# tappytap_v6_AoA_6x6.net
KiCad netlist of a schematic drawn in EAGLE
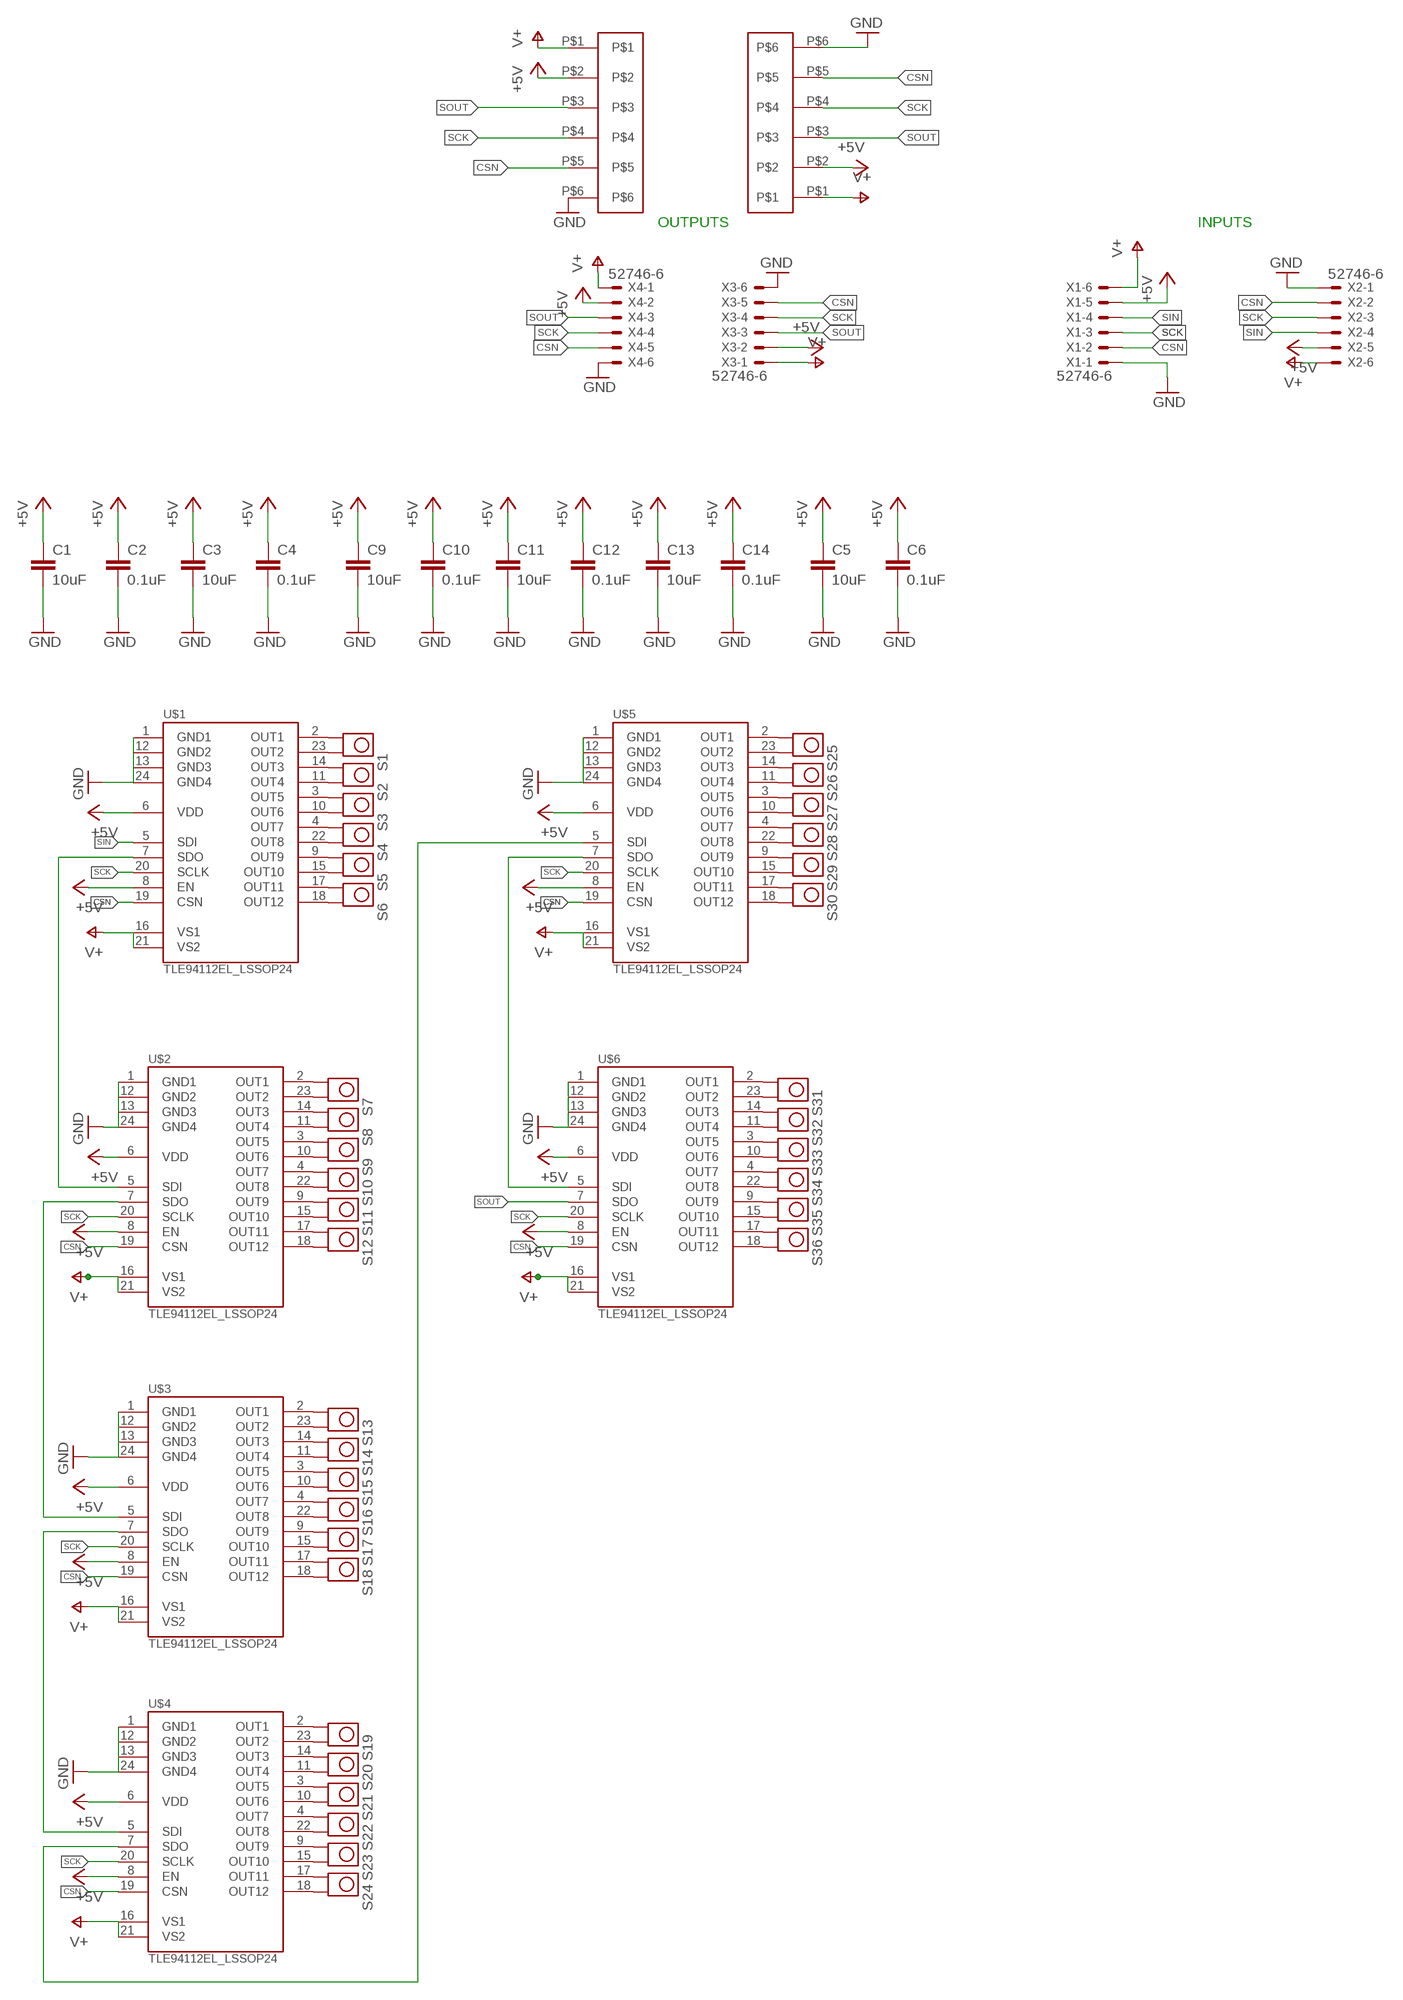
[diagram p0: schematic, sheet 1]

(export (version "E")
  (design (tool "Eeschema 10.0.6"))
  (components
    (comp (ref "C1")
      (value "10uF")
      (footprint "eagle-import:C0603")
      (libsource (lib "eagle-import") (part "C-EUC0603"))
    )
    (comp (ref "C2")
      (value "0.1uF")
      (footprint "eagle-import:C0603")
      (libsource (lib "eagle-import") (part "C-EUC0603"))
    )
    (comp (ref "C3")
      (value "10uF")
      (footprint "eagle-import:C0603")
      (libsource (lib "eagle-import") (part "C-EUC0603"))
    )
    (comp (ref "C4")
      (value "0.1uF")
      (footprint "eagle-import:C0603")
      (libsource (lib "eagle-import") (part "C-EUC0603"))
    )
    (comp (ref "C5")
      (value "10uF")
      (footprint "eagle-import:C0603")
      (libsource (lib "eagle-import") (part "C-EUC0603"))
    )
    (comp (ref "C6")
      (value "0.1uF")
      (footprint "eagle-import:C0603")
      (libsource (lib "eagle-import") (part "C-EUC0603"))
    )
    (comp (ref "C9")
      (value "10uF")
      (footprint "eagle-import:C0603")
      (libsource (lib "eagle-import") (part "C-EUC0603"))
    )
    (comp (ref "C10")
      (value "0.1uF")
      (footprint "eagle-import:C0603")
      (libsource (lib "eagle-import") (part "C-EUC0603"))
    )
    (comp (ref "C11")
      (value "10uF")
      (footprint "eagle-import:C0603")
      (libsource (lib "eagle-import") (part "C-EUC0603"))
    )
    (comp (ref "C12")
      (value "0.1uF")
      (footprint "eagle-import:C0603")
      (libsource (lib "eagle-import") (part "C-EUC0603"))
    )
    (comp (ref "C13")
      (value "10uF")
      (footprint "eagle-import:C0603")
      (libsource (lib "eagle-import") (part "C-EUC0603"))
    )
    (comp (ref "C14")
      (value "0.1uF")
      (footprint "eagle-import:C0603")
      (libsource (lib "eagle-import") (part "C-EUC0603"))
    )
    (comp (ref "S1")
      (value "TP_4MM_MED_PAD")
      (footprint "eagle-import:TP_4MM_MED_PAD")
      (libsource (lib "eagle-import") (part "TP_4MM_MED_PAD"))
    )
    (comp (ref "S2")
      (value "TP_4MM_MED_PAD")
      (footprint "eagle-import:TP_4MM_MED_PAD")
      (libsource (lib "eagle-import") (part "TP_4MM_MED_PAD"))
    )
    (comp (ref "S3")
      (value "TP_4MM_MED_PAD")
      (footprint "eagle-import:TP_4MM_MED_PAD")
      (libsource (lib "eagle-import") (part "TP_4MM_MED_PAD"))
    )
    (comp (ref "S4")
      (value "TP_4MM_MED_PAD")
      (footprint "eagle-import:TP_4MM_MED_PAD")
      (libsource (lib "eagle-import") (part "TP_4MM_MED_PAD"))
    )
    (comp (ref "S5")
      (value "TP_4MM_MED_PAD")
      (footprint "eagle-import:TP_4MM_MED_PAD")
      (libsource (lib "eagle-import") (part "TP_4MM_MED_PAD"))
    )
    (comp (ref "S6")
      (value "TP_4MM_MED_PAD")
      (footprint "eagle-import:TP_4MM_MED_PAD")
      (libsource (lib "eagle-import") (part "TP_4MM_MED_PAD"))
    )
    (comp (ref "S7")
      (value "TP_4MM_MED_PAD")
      (footprint "eagle-import:TP_4MM_MED_PAD")
      (libsource (lib "eagle-import") (part "TP_4MM_MED_PAD"))
    )
    (comp (ref "S8")
      (value "TP_4MM_MED_PAD")
      (footprint "eagle-import:TP_4MM_MED_PAD")
      (libsource (lib "eagle-import") (part "TP_4MM_MED_PAD"))
    )
    (comp (ref "S9")
      (value "TP_4MM_MED_PAD")
      (footprint "eagle-import:TP_4MM_MED_PAD")
      (libsource (lib "eagle-import") (part "TP_4MM_MED_PAD"))
    )
    (comp (ref "S10")
      (value "TP_4MM_MED_PAD")
      (footprint "eagle-import:TP_4MM_MED_PAD")
      (libsource (lib "eagle-import") (part "TP_4MM_MED_PAD"))
    )
    (comp (ref "S11")
      (value "TP_4MM_MED_PAD")
      (footprint "eagle-import:TP_4MM_MED_PAD")
      (libsource (lib "eagle-import") (part "TP_4MM_MED_PAD"))
    )
    (comp (ref "S12")
      (value "TP_4MM_MED_PAD")
      (footprint "eagle-import:TP_4MM_MED_PAD")
      (libsource (lib "eagle-import") (part "TP_4MM_MED_PAD"))
    )
    (comp (ref "S13")
      (value "TP_4MM_MED_PAD")
      (footprint "eagle-import:TP_4MM_MED_PAD")
      (libsource (lib "eagle-import") (part "TP_4MM_MED_PAD"))
    )
    (comp (ref "S14")
      (value "TP_4MM_MED_PAD")
      (footprint "eagle-import:TP_4MM_MED_PAD")
      (libsource (lib "eagle-import") (part "TP_4MM_MED_PAD"))
    )
    (comp (ref "S15")
      (value "TP_4MM_MED_PAD")
      (footprint "eagle-import:TP_4MM_MED_PAD")
      (libsource (lib "eagle-import") (part "TP_4MM_MED_PAD"))
    )
    (comp (ref "S16")
      (value "TP_4MM_MED_PAD")
      (footprint "eagle-import:TP_4MM_MED_PAD")
      (libsource (lib "eagle-import") (part "TP_4MM_MED_PAD"))
    )
    (comp (ref "S17")
      (value "TP_4MM_MED_PAD")
      (footprint "eagle-import:TP_4MM_MED_PAD")
      (libsource (lib "eagle-import") (part "TP_4MM_MED_PAD"))
    )
    (comp (ref "S18")
      (value "TP_4MM_MED_PAD")
      (footprint "eagle-import:TP_4MM_MED_PAD")
      (libsource (lib "eagle-import") (part "TP_4MM_MED_PAD"))
    )
    (comp (ref "S19")
      (value "TP_4MM_MED_PAD")
      (footprint "eagle-import:TP_4MM_MED_PAD")
      (libsource (lib "eagle-import") (part "TP_4MM_MED_PAD"))
    )
    (comp (ref "S20")
      (value "TP_4MM_MED_PAD")
      (footprint "eagle-import:TP_4MM_MED_PAD")
      (libsource (lib "eagle-import") (part "TP_4MM_MED_PAD"))
    )
    (comp (ref "S21")
      (value "TP_4MM_MED_PAD")
      (footprint "eagle-import:TP_4MM_MED_PAD")
      (libsource (lib "eagle-import") (part "TP_4MM_MED_PAD"))
    )
    (comp (ref "S22")
      (value "TP_4MM_MED_PAD")
      (footprint "eagle-import:TP_4MM_MED_PAD")
      (libsource (lib "eagle-import") (part "TP_4MM_MED_PAD"))
    )
    (comp (ref "S23")
      (value "TP_4MM_MED_PAD")
      (footprint "eagle-import:TP_4MM_MED_PAD")
      (libsource (lib "eagle-import") (part "TP_4MM_MED_PAD"))
    )
    (comp (ref "S24")
      (value "TP_4MM_MED_PAD")
      (footprint "eagle-import:TP_4MM_MED_PAD")
      (libsource (lib "eagle-import") (part "TP_4MM_MED_PAD"))
    )
    (comp (ref "S25")
      (value "TP_4MM_MED_PAD")
      (footprint "eagle-import:TP_4MM_MED_PAD")
      (libsource (lib "eagle-import") (part "TP_4MM_MED_PAD"))
    )
    (comp (ref "S26")
      (value "TP_4MM_MED_PAD")
      (footprint "eagle-import:TP_4MM_MED_PAD")
      (libsource (lib "eagle-import") (part "TP_4MM_MED_PAD"))
    )
    (comp (ref "S27")
      (value "TP_4MM_MED_PAD")
      (footprint "eagle-import:TP_4MM_MED_PAD")
      (libsource (lib "eagle-import") (part "TP_4MM_MED_PAD"))
    )
    (comp (ref "S28")
      (value "TP_4MM_MED_PAD")
      (footprint "eagle-import:TP_4MM_MED_PAD")
      (libsource (lib "eagle-import") (part "TP_4MM_MED_PAD"))
    )
    (comp (ref "S29")
      (value "TP_4MM_MED_PAD")
      (footprint "eagle-import:TP_4MM_MED_PAD")
      (libsource (lib "eagle-import") (part "TP_4MM_MED_PAD"))
    )
    (comp (ref "S30")
      (value "TP_4MM_MED_PAD")
      (footprint "eagle-import:TP_4MM_MED_PAD")
      (libsource (lib "eagle-import") (part "TP_4MM_MED_PAD"))
    )
    (comp (ref "S31")
      (value "TP_4MM_MED_PAD")
      (footprint "eagle-import:TP_4MM_MED_PAD")
      (libsource (lib "eagle-import") (part "TP_4MM_MED_PAD"))
    )
    (comp (ref "S32")
      (value "TP_4MM_MED_PAD")
      (footprint "eagle-import:TP_4MM_MED_PAD")
      (libsource (lib "eagle-import") (part "TP_4MM_MED_PAD"))
    )
    (comp (ref "S33")
      (value "TP_4MM_MED_PAD")
      (footprint "eagle-import:TP_4MM_MED_PAD")
      (libsource (lib "eagle-import") (part "TP_4MM_MED_PAD"))
    )
    (comp (ref "S34")
      (value "TP_4MM_MED_PAD")
      (footprint "eagle-import:TP_4MM_MED_PAD")
      (libsource (lib "eagle-import") (part "TP_4MM_MED_PAD"))
    )
    (comp (ref "S35")
      (value "TP_4MM_MED_PAD")
      (footprint "eagle-import:TP_4MM_MED_PAD")
      (libsource (lib "eagle-import") (part "TP_4MM_MED_PAD"))
    )
    (comp (ref "S36")
      (value "TP_4MM_MED_PAD")
      (footprint "eagle-import:TP_4MM_MED_PAD")
      (libsource (lib "eagle-import") (part "TP_4MM_MED_PAD"))
    )
    (comp (ref "U$1")
      (value "TLE94112EL_LSSOP24")
      (footprint "eagle-import:SSOP-24")
      (libsource (lib "eagle-import") (part "TLE94112EL_LSSOP24"))
    )
    (comp (ref "U$2")
      (value "TLE94112EL_LSSOP24")
      (footprint "eagle-import:SSOP-24")
      (libsource (lib "eagle-import") (part "TLE94112EL_LSSOP24"))
    )
    (comp (ref "U$3")
      (value "TLE94112EL_LSSOP24")
      (footprint "eagle-import:SSOP-24")
      (libsource (lib "eagle-import") (part "TLE94112EL_LSSOP24"))
    )
    (comp (ref "U$4")
      (value "TLE94112EL_LSSOP24")
      (footprint "eagle-import:SSOP-24")
      (libsource (lib "eagle-import") (part "TLE94112EL_LSSOP24"))
    )
    (comp (ref "U$5")
      (value "TLE94112EL_LSSOP24")
      (footprint "eagle-import:SSOP-24")
      (libsource (lib "eagle-import") (part "TLE94112EL_LSSOP24"))
    )
    (comp (ref "U$6")
      (value "TLE94112EL_LSSOP24")
      (footprint "eagle-import:SSOP-24")
      (libsource (lib "eagle-import") (part "TLE94112EL_LSSOP24"))
    )
    (comp (ref "U$15")
      (value "FLEXTAB_6POS")
      (footprint "eagle-import:FLEXTAB_6POS")
      (libsource (lib "eagle-import") (part "FLEXTAB_6POS"))
    )
    (comp (ref "U$16")
      (value "FLEXTAB_6POS")
      (footprint "eagle-import:FLEXTAB_6POS")
      (libsource (lib "eagle-import") (part "FLEXTAB_6POS"))
    )
    (comp (ref "X1")
      (value "52746-6")
      (footprint "eagle-import:52746-6")
      (libsource (lib "eagle-import") (part "52746-6"))
    )
    (comp (ref "X2")
      (value "52746-6")
      (footprint "eagle-import:52746-6")
      (libsource (lib "eagle-import") (part "52746-6"))
    )
    (comp (ref "X3")
      (value "52746-6")
      (footprint "eagle-import:52746-6")
      (libsource (lib "eagle-import") (part "52746-6"))
    )
    (comp (ref "X4")
      (value "52746-6")
      (footprint "eagle-import:52746-6")
      (libsource (lib "eagle-import") (part "52746-6"))
    )
  )
  (nets
    (net (code "1") (name "+5V") (class "Default")
      (node (ref "C1") (pin "1") (pinfunction "1_1") (pintype "passive"))
      (node (ref "C10") (pin "1") (pinfunction "1_1") (pintype "passive"))
      (node (ref "C11") (pin "1") (pinfunction "1_1") (pintype "passive"))
      (node (ref "C12") (pin "1") (pinfunction "1_1") (pintype "passive"))
      (node (ref "C13") (pin "1") (pinfunction "1_1") (pintype "passive"))
      (node (ref "C14") (pin "1") (pinfunction "1_1") (pintype "passive"))
      (node (ref "C2") (pin "1") (pinfunction "1_1") (pintype "passive"))
      (node (ref "C3") (pin "1") (pinfunction "1_1") (pintype "passive"))
      (node (ref "C4") (pin "1") (pinfunction "1_1") (pintype "passive"))
      (node (ref "C5") (pin "1") (pinfunction "1_1") (pintype "passive"))
      (node (ref "C6") (pin "1") (pinfunction "1_1") (pintype "passive"))
      (node (ref "C9") (pin "1") (pinfunction "1_1") (pintype "passive"))
      (node (ref "U$1") (pin "6") (pinfunction "VDD_6") (pintype "bidirectional"))
      (node (ref "U$1") (pin "8") (pinfunction "EN_8") (pintype "bidirectional"))
      (node (ref "U$15") (pin "P$2") (pinfunction "P$2_P$2") (pintype "bidirectional"))
      (node (ref "U$16") (pin "P$2") (pinfunction "P$2_P$2") (pintype "bidirectional"))
      (node (ref "U$2") (pin "6") (pinfunction "VDD_6") (pintype "bidirectional"))
      (node (ref "U$2") (pin "8") (pinfunction "EN_8") (pintype "bidirectional"))
      (node (ref "U$3") (pin "6") (pinfunction "VDD_6") (pintype "bidirectional"))
      (node (ref "U$3") (pin "8") (pinfunction "EN_8") (pintype "bidirectional"))
      (node (ref "U$4") (pin "6") (pinfunction "VDD_6") (pintype "bidirectional"))
      (node (ref "U$4") (pin "8") (pinfunction "EN_8") (pintype "bidirectional"))
      (node (ref "U$5") (pin "6") (pinfunction "VDD_6") (pintype "bidirectional"))
      (node (ref "U$5") (pin "8") (pinfunction "EN_8") (pintype "bidirectional"))
      (node (ref "U$6") (pin "6") (pinfunction "VDD_6") (pintype "bidirectional"))
      (node (ref "U$6") (pin "8") (pinfunction "EN_8") (pintype "bidirectional"))
      (node (ref "X1") (pin "5") (pinfunction "S_5") (pintype "passive"))
      (node (ref "X2") (pin "5") (pinfunction "S_5") (pintype "passive"))
      (node (ref "X3") (pin "2") (pinfunction "S_2") (pintype "passive"))
      (node (ref "X4") (pin "2") (pinfunction "S_2") (pintype "passive"))
    )
    (net (code "2") (name "CSN") (class "Default")
      (node (ref "U$1") (pin "19") (pinfunction "CSN_19") (pintype "bidirectional"))
      (node (ref "U$15") (pin "P$5") (pinfunction "P$5_P$5") (pintype "bidirectional"))
      (node (ref "U$16") (pin "P$5") (pinfunction "P$5_P$5") (pintype "bidirectional"))
      (node (ref "U$2") (pin "19") (pinfunction "CSN_19") (pintype "bidirectional"))
      (node (ref "U$3") (pin "19") (pinfunction "CSN_19") (pintype "bidirectional"))
      (node (ref "U$4") (pin "19") (pinfunction "CSN_19") (pintype "bidirectional"))
      (node (ref "U$5") (pin "19") (pinfunction "CSN_19") (pintype "bidirectional"))
      (node (ref "U$6") (pin "19") (pinfunction "CSN_19") (pintype "bidirectional"))
      (node (ref "X1") (pin "2") (pinfunction "S_2") (pintype "passive"))
      (node (ref "X2") (pin "2") (pinfunction "S_2") (pintype "passive"))
      (node (ref "X3") (pin "5") (pinfunction "S_5") (pintype "passive"))
      (node (ref "X4") (pin "5") (pinfunction "S_5") (pintype "passive"))
    )
    (net (code "3") (name "GND") (class "Default")
      (node (ref "C1") (pin "2") (pinfunction "2_2") (pintype "passive"))
      (node (ref "C10") (pin "2") (pinfunction "2_2") (pintype "passive"))
      (node (ref "C11") (pin "2") (pinfunction "2_2") (pintype "passive"))
      (node (ref "C12") (pin "2") (pinfunction "2_2") (pintype "passive"))
      (node (ref "C13") (pin "2") (pinfunction "2_2") (pintype "passive"))
      (node (ref "C14") (pin "2") (pinfunction "2_2") (pintype "passive"))
      (node (ref "C2") (pin "2") (pinfunction "2_2") (pintype "passive"))
      (node (ref "C3") (pin "2") (pinfunction "2_2") (pintype "passive"))
      (node (ref "C4") (pin "2") (pinfunction "2_2") (pintype "passive"))
      (node (ref "C5") (pin "2") (pinfunction "2_2") (pintype "passive"))
      (node (ref "C6") (pin "2") (pinfunction "2_2") (pintype "passive"))
      (node (ref "C9") (pin "2") (pinfunction "2_2") (pintype "passive"))
      (node (ref "U$1") (pin "1") (pinfunction "GND1_1") (pintype "bidirectional"))
      (node (ref "U$1") (pin "12") (pinfunction "GND2_12") (pintype "bidirectional"))
      (node (ref "U$1") (pin "13") (pinfunction "GND3_13") (pintype "bidirectional"))
      (node (ref "U$1") (pin "24") (pinfunction "GND4_24") (pintype "bidirectional"))
      (node (ref "U$15") (pin "P$6") (pinfunction "P$6_P$6") (pintype "bidirectional"))
      (node (ref "U$16") (pin "P$6") (pinfunction "P$6_P$6") (pintype "bidirectional"))
      (node (ref "U$2") (pin "1") (pinfunction "GND1_1") (pintype "bidirectional"))
      (node (ref "U$2") (pin "12") (pinfunction "GND2_12") (pintype "bidirectional"))
      (node (ref "U$2") (pin "13") (pinfunction "GND3_13") (pintype "bidirectional"))
      (node (ref "U$2") (pin "24") (pinfunction "GND4_24") (pintype "bidirectional"))
      (node (ref "U$3") (pin "1") (pinfunction "GND1_1") (pintype "bidirectional"))
      (node (ref "U$3") (pin "12") (pinfunction "GND2_12") (pintype "bidirectional"))
      (node (ref "U$3") (pin "13") (pinfunction "GND3_13") (pintype "bidirectional"))
      (node (ref "U$3") (pin "24") (pinfunction "GND4_24") (pintype "bidirectional"))
      (node (ref "U$4") (pin "1") (pinfunction "GND1_1") (pintype "bidirectional"))
      (node (ref "U$4") (pin "12") (pinfunction "GND2_12") (pintype "bidirectional"))
      (node (ref "U$4") (pin "13") (pinfunction "GND3_13") (pintype "bidirectional"))
      (node (ref "U$4") (pin "24") (pinfunction "GND4_24") (pintype "bidirectional"))
      (node (ref "U$5") (pin "1") (pinfunction "GND1_1") (pintype "bidirectional"))
      (node (ref "U$5") (pin "12") (pinfunction "GND2_12") (pintype "bidirectional"))
      (node (ref "U$5") (pin "13") (pinfunction "GND3_13") (pintype "bidirectional"))
      (node (ref "U$5") (pin "24") (pinfunction "GND4_24") (pintype "bidirectional"))
      (node (ref "U$6") (pin "1") (pinfunction "GND1_1") (pintype "bidirectional"))
      (node (ref "U$6") (pin "12") (pinfunction "GND2_12") (pintype "bidirectional"))
      (node (ref "U$6") (pin "13") (pinfunction "GND3_13") (pintype "bidirectional"))
      (node (ref "U$6") (pin "24") (pinfunction "GND4_24") (pintype "bidirectional"))
      (node (ref "X1") (pin "1") (pinfunction "S_1") (pintype "passive"))
      (node (ref "X2") (pin "1") (pinfunction "S_1") (pintype "passive"))
      (node (ref "X3") (pin "6") (pinfunction "S_6") (pintype "passive"))
      (node (ref "X4") (pin "6") (pinfunction "S_6") (pintype "passive"))
    )
    (net (code "4") (name "Net-(S1-0)") (class "Default")
      (node (ref "S1") (pin "P$1") (pinfunction "0_P$1") (pintype "bidirectional"))
      (node (ref "U$1") (pin "2") (pinfunction "OUT1_2") (pintype "bidirectional"))
    )
    (net (code "5") (name "Net-(S1-1)") (class "Default")
      (node (ref "S1") (pin "P$2") (pinfunction "1_P$2") (pintype "bidirectional"))
      (node (ref "U$1") (pin "23") (pinfunction "OUT2_23") (pintype "bidirectional"))
    )
    (net (code "6") (name "Net-(S2-0)") (class "Default")
      (node (ref "S2") (pin "P$1") (pinfunction "0_P$1") (pintype "bidirectional"))
      (node (ref "U$1") (pin "14") (pinfunction "OUT3_14") (pintype "bidirectional"))
    )
    (net (code "7") (name "Net-(S2-1)") (class "Default")
      (node (ref "S2") (pin "P$2") (pinfunction "1_P$2") (pintype "bidirectional"))
      (node (ref "U$1") (pin "11") (pinfunction "OUT4_11") (pintype "bidirectional"))
    )
    (net (code "8") (name "Net-(S3-0)") (class "Default")
      (node (ref "S3") (pin "P$1") (pinfunction "0_P$1") (pintype "bidirectional"))
      (node (ref "U$1") (pin "3") (pinfunction "OUT5_3") (pintype "bidirectional"))
    )
    (net (code "9") (name "Net-(S3-1)") (class "Default")
      (node (ref "S3") (pin "P$2") (pinfunction "1_P$2") (pintype "bidirectional"))
      (node (ref "U$1") (pin "10") (pinfunction "OUT6_10") (pintype "bidirectional"))
    )
    (net (code "10") (name "Net-(S4-0)") (class "Default")
      (node (ref "S4") (pin "P$1") (pinfunction "0_P$1") (pintype "bidirectional"))
      (node (ref "U$1") (pin "4") (pinfunction "OUT7_4") (pintype "bidirectional"))
    )
    (net (code "11") (name "Net-(S4-1)") (class "Default")
      (node (ref "S4") (pin "P$2") (pinfunction "1_P$2") (pintype "bidirectional"))
      (node (ref "U$1") (pin "22") (pinfunction "OUT8_22") (pintype "bidirectional"))
    )
    (net (code "12") (name "Net-(S5-0)") (class "Default")
      (node (ref "S5") (pin "P$1") (pinfunction "0_P$1") (pintype "bidirectional"))
      (node (ref "U$1") (pin "9") (pinfunction "OUT9_9") (pintype "bidirectional"))
    )
    (net (code "13") (name "Net-(S5-1)") (class "Default")
      (node (ref "S5") (pin "P$2") (pinfunction "1_P$2") (pintype "bidirectional"))
      (node (ref "U$1") (pin "15") (pinfunction "OUT10_15") (pintype "bidirectional"))
    )
    (net (code "14") (name "Net-(S6-0)") (class "Default")
      (node (ref "S6") (pin "P$1") (pinfunction "0_P$1") (pintype "bidirectional"))
      (node (ref "U$1") (pin "17") (pinfunction "OUT11_17") (pintype "bidirectional"))
    )
    (net (code "15") (name "Net-(S6-1)") (class "Default")
      (node (ref "S6") (pin "P$2") (pinfunction "1_P$2") (pintype "bidirectional"))
      (node (ref "U$1") (pin "18") (pinfunction "OUT12_18") (pintype "bidirectional"))
    )
    (net (code "16") (name "Net-(S7-0)") (class "Default")
      (node (ref "S7") (pin "P$1") (pinfunction "0_P$1") (pintype "bidirectional"))
      (node (ref "U$2") (pin "2") (pinfunction "OUT1_2") (pintype "bidirectional"))
    )
    (net (code "17") (name "Net-(S7-1)") (class "Default")
      (node (ref "S7") (pin "P$2") (pinfunction "1_P$2") (pintype "bidirectional"))
      (node (ref "U$2") (pin "23") (pinfunction "OUT2_23") (pintype "bidirectional"))
    )
    (net (code "18") (name "Net-(S8-0)") (class "Default")
      (node (ref "S8") (pin "P$1") (pinfunction "0_P$1") (pintype "bidirectional"))
      (node (ref "U$2") (pin "14") (pinfunction "OUT3_14") (pintype "bidirectional"))
    )
    (net (code "19") (name "Net-(S8-1)") (class "Default")
      (node (ref "S8") (pin "P$2") (pinfunction "1_P$2") (pintype "bidirectional"))
      (node (ref "U$2") (pin "11") (pinfunction "OUT4_11") (pintype "bidirectional"))
    )
    (net (code "20") (name "Net-(S9-0)") (class "Default")
      (node (ref "S9") (pin "P$1") (pinfunction "0_P$1") (pintype "bidirectional"))
      (node (ref "U$2") (pin "3") (pinfunction "OUT5_3") (pintype "bidirectional"))
    )
    (net (code "21") (name "Net-(S9-1)") (class "Default")
      (node (ref "S9") (pin "P$2") (pinfunction "1_P$2") (pintype "bidirectional"))
      (node (ref "U$2") (pin "10") (pinfunction "OUT6_10") (pintype "bidirectional"))
    )
    (net (code "22") (name "Net-(S10-0)") (class "Default")
      (node (ref "S10") (pin "P$1") (pinfunction "0_P$1") (pintype "bidirectional"))
      (node (ref "U$2") (pin "4") (pinfunction "OUT7_4") (pintype "bidirectional"))
    )
    (net (code "23") (name "Net-(S10-1)") (class "Default")
      (node (ref "S10") (pin "P$2") (pinfunction "1_P$2") (pintype "bidirectional"))
      (node (ref "U$2") (pin "22") (pinfunction "OUT8_22") (pintype "bidirectional"))
    )
    (net (code "24") (name "Net-(S11-0)") (class "Default")
      (node (ref "S11") (pin "P$1") (pinfunction "0_P$1") (pintype "bidirectional"))
      (node (ref "U$2") (pin "9") (pinfunction "OUT9_9") (pintype "bidirectional"))
    )
    (net (code "25") (name "Net-(S11-1)") (class "Default")
      (node (ref "S11") (pin "P$2") (pinfunction "1_P$2") (pintype "bidirectional"))
      (node (ref "U$2") (pin "15") (pinfunction "OUT10_15") (pintype "bidirectional"))
    )
    (net (code "26") (name "Net-(S12-0)") (class "Default")
      (node (ref "S12") (pin "P$1") (pinfunction "0_P$1") (pintype "bidirectional"))
      (node (ref "U$2") (pin "17") (pinfunction "OUT11_17") (pintype "bidirectional"))
    )
    (net (code "27") (name "Net-(S12-1)") (class "Default")
      (node (ref "S12") (pin "P$2") (pinfunction "1_P$2") (pintype "bidirectional"))
      (node (ref "U$2") (pin "18") (pinfunction "OUT12_18") (pintype "bidirectional"))
    )
    (net (code "28") (name "Net-(S13-0)") (class "Default")
      (node (ref "S13") (pin "P$1") (pinfunction "0_P$1") (pintype "bidirectional"))
      (node (ref "U$3") (pin "2") (pinfunction "OUT1_2") (pintype "bidirectional"))
    )
    (net (code "29") (name "Net-(S13-1)") (class "Default")
      (node (ref "S13") (pin "P$2") (pinfunction "1_P$2") (pintype "bidirectional"))
      (node (ref "U$3") (pin "23") (pinfunction "OUT2_23") (pintype "bidirectional"))
    )
    (net (code "30") (name "Net-(S14-0)") (class "Default")
      (node (ref "S14") (pin "P$1") (pinfunction "0_P$1") (pintype "bidirectional"))
      (node (ref "U$3") (pin "14") (pinfunction "OUT3_14") (pintype "bidirectional"))
    )
    (net (code "31") (name "Net-(S14-1)") (class "Default")
      (node (ref "S14") (pin "P$2") (pinfunction "1_P$2") (pintype "bidirectional"))
      (node (ref "U$3") (pin "11") (pinfunction "OUT4_11") (pintype "bidirectional"))
    )
    (net (code "32") (name "Net-(S15-0)") (class "Default")
      (node (ref "S15") (pin "P$1") (pinfunction "0_P$1") (pintype "bidirectional"))
      (node (ref "U$3") (pin "3") (pinfunction "OUT5_3") (pintype "bidirectional"))
    )
    (net (code "33") (name "Net-(S15-1)") (class "Default")
      (node (ref "S15") (pin "P$2") (pinfunction "1_P$2") (pintype "bidirectional"))
      (node (ref "U$3") (pin "10") (pinfunction "OUT6_10") (pintype "bidirectional"))
    )
    (net (code "34") (name "Net-(S16-0)") (class "Default")
      (node (ref "S16") (pin "P$1") (pinfunction "0_P$1") (pintype "bidirectional"))
      (node (ref "U$3") (pin "4") (pinfunction "OUT7_4") (pintype "bidirectional"))
    )
    (net (code "35") (name "Net-(S16-1)") (class "Default")
      (node (ref "S16") (pin "P$2") (pinfunction "1_P$2") (pintype "bidirectional"))
      (node (ref "U$3") (pin "22") (pinfunction "OUT8_22") (pintype "bidirectional"))
    )
    (net (code "36") (name "Net-(S17-0)") (class "Default")
      (node (ref "S17") (pin "P$1") (pinfunction "0_P$1") (pintype "bidirectional"))
      (node (ref "U$3") (pin "9") (pinfunction "OUT9_9") (pintype "bidirectional"))
    )
    (net (code "37") (name "Net-(S17-1)") (class "Default")
      (node (ref "S17") (pin "P$2") (pinfunction "1_P$2") (pintype "bidirectional"))
      (node (ref "U$3") (pin "15") (pinfunction "OUT10_15") (pintype "bidirectional"))
    )
    (net (code "38") (name "Net-(S18-0)") (class "Default")
      (node (ref "S18") (pin "P$1") (pinfunction "0_P$1") (pintype "bidirectional"))
      (node (ref "U$3") (pin "17") (pinfunction "OUT11_17") (pintype "bidirectional"))
    )
    (net (code "39") (name "Net-(S18-1)") (class "Default")
      (node (ref "S18") (pin "P$2") (pinfunction "1_P$2") (pintype "bidirectional"))
      (node (ref "U$3") (pin "18") (pinfunction "OUT12_18") (pintype "bidirectional"))
    )
    (net (code "40") (name "Net-(S19-0)") (class "Default")
      (node (ref "S19") (pin "P$1") (pinfunction "0_P$1") (pintype "bidirectional"))
      (node (ref "U$4") (pin "2") (pinfunction "OUT1_2") (pintype "bidirectional"))
    )
    (net (code "41") (name "Net-(S19-1)") (class "Default")
      (node (ref "S19") (pin "P$2") (pinfunction "1_P$2") (pintype "bidirectional"))
      (node (ref "U$4") (pin "23") (pinfunction "OUT2_23") (pintype "bidirectional"))
    )
    (net (code "42") (name "Net-(S20-0)") (class "Default")
      (node (ref "S20") (pin "P$1") (pinfunction "0_P$1") (pintype "bidirectional"))
      (node (ref "U$4") (pin "14") (pinfunction "OUT3_14") (pintype "bidirectional"))
    )
    (net (code "43") (name "Net-(S20-1)") (class "Default")
      (node (ref "S20") (pin "P$2") (pinfunction "1_P$2") (pintype "bidirectional"))
      (node (ref "U$4") (pin "11") (pinfunction "OUT4_11") (pintype "bidirectional"))
    )
    (net (code "44") (name "Net-(S21-0)") (class "Default")
      (node (ref "S21") (pin "P$1") (pinfunction "0_P$1") (pintype "bidirectional"))
      (node (ref "U$4") (pin "3") (pinfunction "OUT5_3") (pintype "bidirectional"))
    )
    (net (code "45") (name "Net-(S21-1)") (class "Default")
      (node (ref "S21") (pin "P$2") (pinfunction "1_P$2") (pintype "bidirectional"))
      (node (ref "U$4") (pin "10") (pinfunction "OUT6_10") (pintype "bidirectional"))
    )
    (net (code "46") (name "Net-(S22-0)") (class "Default")
      (node (ref "S22") (pin "P$1") (pinfunction "0_P$1") (pintype "bidirectional"))
      (node (ref "U$4") (pin "4") (pinfunction "OUT7_4") (pintype "bidirectional"))
    )
    (net (code "47") (name "Net-(S22-1)") (class "Default")
      (node (ref "S22") (pin "P$2") (pinfunction "1_P$2") (pintype "bidirectional"))
      (node (ref "U$4") (pin "22") (pinfunction "OUT8_22") (pintype "bidirectional"))
    )
    (net (code "48") (name "Net-(S23-0)") (class "Default")
      (node (ref "S23") (pin "P$1") (pinfunction "0_P$1") (pintype "bidirectional"))
      (node (ref "U$4") (pin "9") (pinfunction "OUT9_9") (pintype "bidirectional"))
    )
    (net (code "49") (name "Net-(S23-1)") (class "Default")
      (node (ref "S23") (pin "P$2") (pinfunction "1_P$2") (pintype "bidirectional"))
      (node (ref "U$4") (pin "15") (pinfunction "OUT10_15") (pintype "bidirectional"))
    )
    (net (code "50") (name "Net-(S24-0)") (class "Default")
      (node (ref "S24") (pin "P$1") (pinfunction "0_P$1") (pintype "bidirectional"))
      (node (ref "U$4") (pin "17") (pinfunction "OUT11_17") (pintype "bidirectional"))
    )
    (net (code "51") (name "Net-(S24-1)") (class "Default")
      (node (ref "S24") (pin "P$2") (pinfunction "1_P$2") (pintype "bidirectional"))
      (node (ref "U$4") (pin "18") (pinfunction "OUT12_18") (pintype "bidirectional"))
    )
    (net (code "52") (name "Net-(S25-0)") (class "Default")
      (node (ref "S25") (pin "P$1") (pinfunction "0_P$1") (pintype "bidirectional"))
      (node (ref "U$5") (pin "2") (pinfunction "OUT1_2") (pintype "bidirectional"))
    )
    (net (code "53") (name "Net-(S25-1)") (class "Default")
      (node (ref "S25") (pin "P$2") (pinfunction "1_P$2") (pintype "bidirectional"))
      (node (ref "U$5") (pin "23") (pinfunction "OUT2_23") (pintype "bidirectional"))
    )
    (net (code "54") (name "Net-(S26-0)") (class "Default")
      (node (ref "S26") (pin "P$1") (pinfunction "0_P$1") (pintype "bidirectional"))
      (node (ref "U$5") (pin "14") (pinfunction "OUT3_14") (pintype "bidirectional"))
    )
    (net (code "55") (name "Net-(S26-1)") (class "Default")
      (node (ref "S26") (pin "P$2") (pinfunction "1_P$2") (pintype "bidirectional"))
      (node (ref "U$5") (pin "11") (pinfunction "OUT4_11") (pintype "bidirectional"))
    )
    (net (code "56") (name "Net-(S27-0)") (class "Default")
      (node (ref "S27") (pin "P$1") (pinfunction "0_P$1") (pintype "bidirectional"))
      (node (ref "U$5") (pin "3") (pinfunction "OUT5_3") (pintype "bidirectional"))
    )
    (net (code "57") (name "Net-(S27-1)") (class "Default")
      (node (ref "S27") (pin "P$2") (pinfunction "1_P$2") (pintype "bidirectional"))
      (node (ref "U$5") (pin "10") (pinfunction "OUT6_10") (pintype "bidirectional"))
    )
    (net (code "58") (name "Net-(S28-0)") (class "Default")
      (node (ref "S28") (pin "P$1") (pinfunction "0_P$1") (pintype "bidirectional"))
      (node (ref "U$5") (pin "4") (pinfunction "OUT7_4") (pintype "bidirectional"))
    )
    (net (code "59") (name "Net-(S28-1)") (class "Default")
      (node (ref "S28") (pin "P$2") (pinfunction "1_P$2") (pintype "bidirectional"))
      (node (ref "U$5") (pin "22") (pinfunction "OUT8_22") (pintype "bidirectional"))
    )
    (net (code "60") (name "Net-(S29-0)") (class "Default")
      (node (ref "S29") (pin "P$1") (pinfunction "0_P$1") (pintype "bidirectional"))
      (node (ref "U$5") (pin "9") (pinfunction "OUT9_9") (pintype "bidirectional"))
    )
    (net (code "61") (name "Net-(S29-1)") (class "Default")
      (node (ref "S29") (pin "P$2") (pinfunction "1_P$2") (pintype "bidirectional"))
      (node (ref "U$5") (pin "15") (pinfunction "OUT10_15") (pintype "bidirectional"))
    )
    (net (code "62") (name "Net-(S30-0)") (class "Default")
      (node (ref "S30") (pin "P$1") (pinfunction "0_P$1") (pintype "bidirectional"))
      (node (ref "U$5") (pin "17") (pinfunction "OUT11_17") (pintype "bidirectional"))
    )
    (net (code "63") (name "Net-(S30-1)") (class "Default")
      (node (ref "S30") (pin "P$2") (pinfunction "1_P$2") (pintype "bidirectional"))
      (node (ref "U$5") (pin "18") (pinfunction "OUT12_18") (pintype "bidirectional"))
    )
    (net (code "64") (name "Net-(S31-0)") (class "Default")
      (node (ref "S31") (pin "P$1") (pinfunction "0_P$1") (pintype "bidirectional"))
      (node (ref "U$6") (pin "2") (pinfunction "OUT1_2") (pintype "bidirectional"))
    )
    (net (code "65") (name "Net-(S31-1)") (class "Default")
      (node (ref "S31") (pin "P$2") (pinfunction "1_P$2") (pintype "bidirectional"))
      (node (ref "U$6") (pin "23") (pinfunction "OUT2_23") (pintype "bidirectional"))
    )
    (net (code "66") (name "Net-(S32-0)") (class "Default")
      (node (ref "S32") (pin "P$1") (pinfunction "0_P$1") (pintype "bidirectional"))
      (node (ref "U$6") (pin "14") (pinfunction "OUT3_14") (pintype "bidirectional"))
    )
    (net (code "67") (name "Net-(S32-1)") (class "Default")
      (node (ref "S32") (pin "P$2") (pinfunction "1_P$2") (pintype "bidirectional"))
      (node (ref "U$6") (pin "11") (pinfunction "OUT4_11") (pintype "bidirectional"))
    )
    (net (code "68") (name "Net-(S33-0)") (class "Default")
      (node (ref "S33") (pin "P$1") (pinfunction "0_P$1") (pintype "bidirectional"))
      (node (ref "U$6") (pin "3") (pinfunction "OUT5_3") (pintype "bidirectional"))
    )
    (net (code "69") (name "Net-(S33-1)") (class "Default")
      (node (ref "S33") (pin "P$2") (pinfunction "1_P$2") (pintype "bidirectional"))
      (node (ref "U$6") (pin "10") (pinfunction "OUT6_10") (pintype "bidirectional"))
    )
    (net (code "70") (name "Net-(S34-0)") (class "Default")
      (node (ref "S34") (pin "P$1") (pinfunction "0_P$1") (pintype "bidirectional"))
      (node (ref "U$6") (pin "4") (pinfunction "OUT7_4") (pintype "bidirectional"))
    )
    (net (code "71") (name "Net-(S34-1)") (class "Default")
      (node (ref "S34") (pin "P$2") (pinfunction "1_P$2") (pintype "bidirectional"))
      (node (ref "U$6") (pin "22") (pinfunction "OUT8_22") (pintype "bidirectional"))
    )
    (net (code "72") (name "Net-(S35-0)") (class "Default")
      (node (ref "S35") (pin "P$1") (pinfunction "0_P$1") (pintype "bidirectional"))
      (node (ref "U$6") (pin "9") (pinfunction "OUT9_9") (pintype "bidirectional"))
    )
    (net (code "73") (name "Net-(S35-1)") (class "Default")
      (node (ref "S35") (pin "P$2") (pinfunction "1_P$2") (pintype "bidirectional"))
      (node (ref "U$6") (pin "15") (pinfunction "OUT10_15") (pintype "bidirectional"))
    )
    (net (code "74") (name "Net-(S36-0)") (class "Default")
      (node (ref "S36") (pin "P$1") (pinfunction "0_P$1") (pintype "bidirectional"))
      (node (ref "U$6") (pin "17") (pinfunction "OUT11_17") (pintype "bidirectional"))
    )
    (net (code "75") (name "Net-(S36-1)") (class "Default")
      (node (ref "S36") (pin "P$2") (pinfunction "1_P$2") (pintype "bidirectional"))
      (node (ref "U$6") (pin "18") (pinfunction "OUT12_18") (pintype "bidirectional"))
    )
    (net (code "76") (name "Net-(U$1-SDO)") (class "Default")
      (node (ref "U$1") (pin "7") (pinfunction "SDO_7") (pintype "bidirectional"))
      (node (ref "U$2") (pin "5") (pinfunction "SDI_5") (pintype "bidirectional"))
    )
    (net (code "77") (name "Net-(U$2-SDO)") (class "Default")
      (node (ref "U$2") (pin "7") (pinfunction "SDO_7") (pintype "bidirectional"))
      (node (ref "U$3") (pin "5") (pinfunction "SDI_5") (pintype "bidirectional"))
    )
    (net (code "78") (name "Net-(U$3-SDO)") (class "Default")
      (node (ref "U$3") (pin "7") (pinfunction "SDO_7") (pintype "bidirectional"))
      (node (ref "U$4") (pin "5") (pinfunction "SDI_5") (pintype "bidirectional"))
    )
    (net (code "79") (name "Net-(U$4-SDO)") (class "Default")
      (node (ref "U$4") (pin "7") (pinfunction "SDO_7") (pintype "bidirectional"))
      (node (ref "U$5") (pin "5") (pinfunction "SDI_5") (pintype "bidirectional"))
    )
    (net (code "80") (name "Net-(U$5-SDO)") (class "Default")
      (node (ref "U$5") (pin "7") (pinfunction "SDO_7") (pintype "bidirectional"))
      (node (ref "U$6") (pin "5") (pinfunction "SDI_5") (pintype "bidirectional"))
    )
    (net (code "81") (name "SCK") (class "Default")
      (node (ref "U$1") (pin "20") (pinfunction "SCLK_20") (pintype "bidirectional"))
      (node (ref "U$15") (pin "P$4") (pinfunction "P$4_P$4") (pintype "bidirectional"))
      (node (ref "U$16") (pin "P$4") (pinfunction "P$4_P$4") (pintype "bidirectional"))
      (node (ref "U$2") (pin "20") (pinfunction "SCLK_20") (pintype "bidirectional"))
      (node (ref "U$3") (pin "20") (pinfunction "SCLK_20") (pintype "bidirectional"))
      (node (ref "U$4") (pin "20") (pinfunction "SCLK_20") (pintype "bidirectional"))
      (node (ref "U$5") (pin "20") (pinfunction "SCLK_20") (pintype "bidirectional"))
      (node (ref "U$6") (pin "20") (pinfunction "SCLK_20") (pintype "bidirectional"))
      (node (ref "X1") (pin "3") (pinfunction "S_3") (pintype "passive"))
      (node (ref "X2") (pin "3") (pinfunction "S_3") (pintype "passive"))
      (node (ref "X3") (pin "4") (pinfunction "S_4") (pintype "passive"))
      (node (ref "X4") (pin "4") (pinfunction "S_4") (pintype "passive"))
    )
    (net (code "82") (name "SIN") (class "Default")
      (node (ref "U$1") (pin "5") (pinfunction "SDI_5") (pintype "bidirectional"))
      (node (ref "X1") (pin "4") (pinfunction "S_4") (pintype "passive"))
      (node (ref "X2") (pin "4") (pinfunction "S_4") (pintype "passive"))
    )
    (net (code "83") (name "SOUT") (class "Default")
      (node (ref "U$15") (pin "P$3") (pinfunction "P$3_P$3") (pintype "bidirectional"))
      (node (ref "U$16") (pin "P$3") (pinfunction "P$3_P$3") (pintype "bidirectional"))
      (node (ref "U$6") (pin "7") (pinfunction "SDO_7") (pintype "bidirectional"))
      (node (ref "X3") (pin "3") (pinfunction "S_3") (pintype "passive"))
      (node (ref "X4") (pin "3") (pinfunction "S_3") (pintype "passive"))
    )
    (net (code "84") (name "V+") (class "Default")
      (node (ref "U$1") (pin "16") (pinfunction "VS1_16") (pintype "bidirectional"))
      (node (ref "U$1") (pin "21") (pinfunction "VS2_21") (pintype "bidirectional"))
      (node (ref "U$15") (pin "P$1") (pinfunction "P$1_P$1") (pintype "bidirectional"))
      (node (ref "U$16") (pin "P$1") (pinfunction "P$1_P$1") (pintype "bidirectional"))
      (node (ref "U$2") (pin "16") (pinfunction "VS1_16") (pintype "bidirectional"))
      (node (ref "U$2") (pin "21") (pinfunction "VS2_21") (pintype "bidirectional"))
      (node (ref "U$3") (pin "16") (pinfunction "VS1_16") (pintype "bidirectional"))
      (node (ref "U$3") (pin "21") (pinfunction "VS2_21") (pintype "bidirectional"))
      (node (ref "U$4") (pin "16") (pinfunction "VS1_16") (pintype "bidirectional"))
      (node (ref "U$4") (pin "21") (pinfunction "VS2_21") (pintype "bidirectional"))
      (node (ref "U$5") (pin "16") (pinfunction "VS1_16") (pintype "bidirectional"))
      (node (ref "U$5") (pin "21") (pinfunction "VS2_21") (pintype "bidirectional"))
      (node (ref "U$6") (pin "16") (pinfunction "VS1_16") (pintype "bidirectional"))
      (node (ref "U$6") (pin "21") (pinfunction "VS2_21") (pintype "bidirectional"))
      (node (ref "X1") (pin "6") (pinfunction "S_6") (pintype "passive"))
      (node (ref "X2") (pin "6") (pinfunction "S_6") (pintype "passive"))
      (node (ref "X3") (pin "1") (pinfunction "S_1") (pintype "passive"))
      (node (ref "X4") (pin "1") (pinfunction "S_1") (pintype "passive"))
    )
  )
)
